# power.net
KiCad netlist of a schematic drawn in Altium Designer
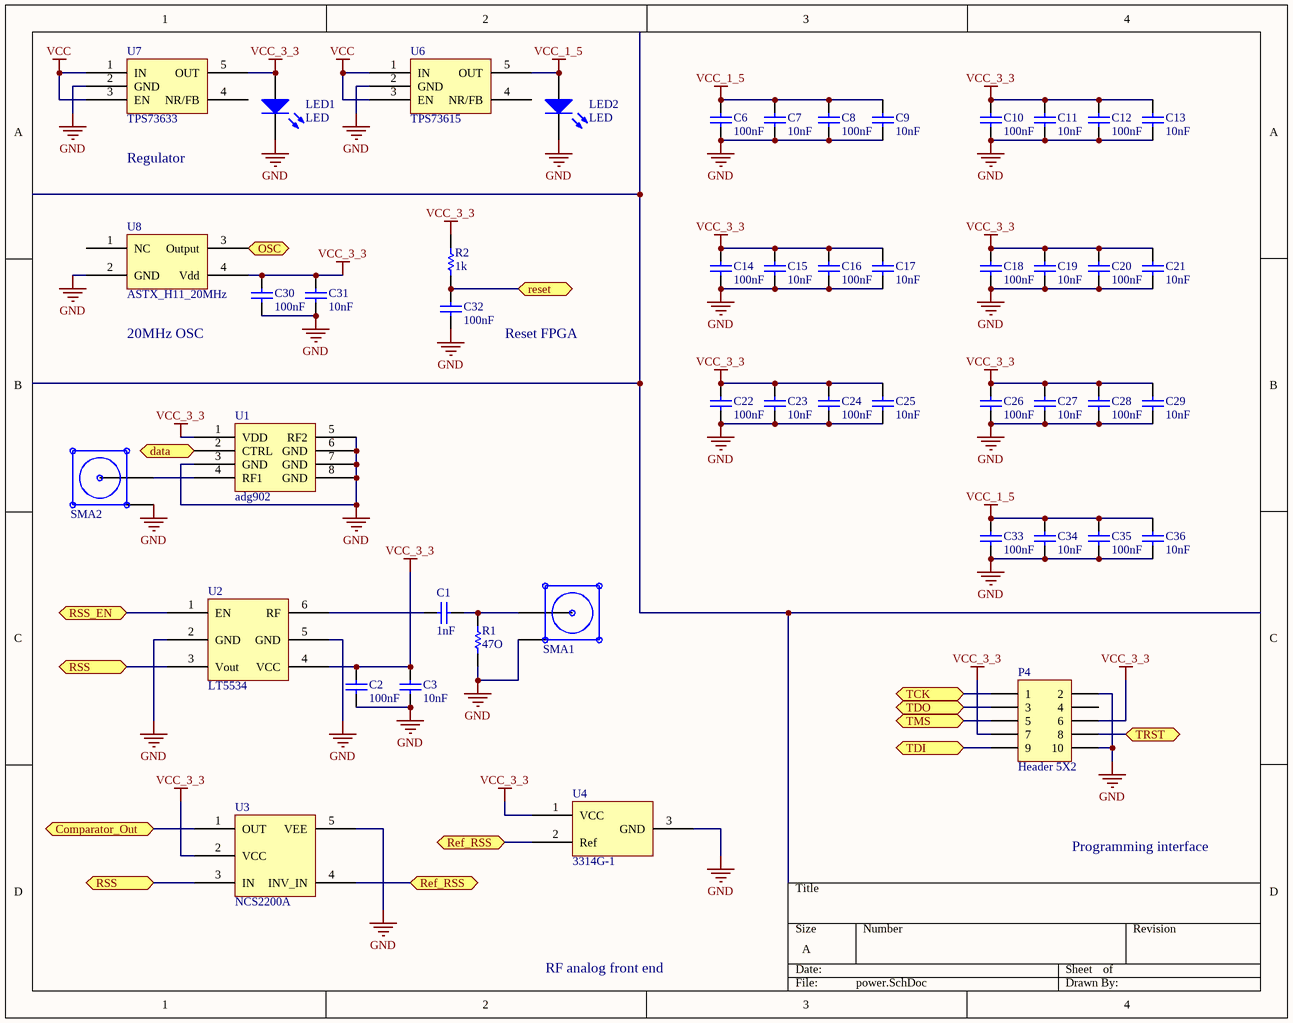
[diagram p0: power.SchDoc]

(export (version "E")
  (design (tool "Eeschema 10.0.6"))
  (components
    (comp (ref "C1")
      (value "1nF")
      (footprint "0603")
      (description "Ceramic Capacitor (Surface Mount)")
      (fields (field (name "MANUFACTURER") "Generic Ceramic Chip Cap (TBD)") (field (name "Comment") "Cap"))
      (libsource (lib "wisp") (part "Cap"))
    )
    (comp (ref "C2")
      (value "100nF")
      (footprint "0603")
      (description "Ceramic Capacitor (Surface Mount)")
      (fields (field (name "MANUFACTURER") "Generic Ceramic Chip Cap (TBD)") (field (name "Comment") "Cap"))
      (libsource (lib "wisp") (part "Cap"))
    )
    (comp (ref "C3")
      (value "10nF")
      (footprint "0603")
      (description "Ceramic Capacitor (Surface Mount)")
      (fields (field (name "MANUFACTURER") "Generic Ceramic Chip Cap (TBD)") (field (name "Comment") "Cap"))
      (libsource (lib "wisp") (part "Cap"))
    )
    (comp (ref "C6")
      (value "100nF")
      (footprint "0603")
      (description "Ceramic Capacitor (Surface Mount)")
      (fields (field (name "MANUFACTURER") "Generic Ceramic Chip Cap (TBD)") (field (name "Comment") "Cap"))
      (libsource (lib "wisp") (part "Cap"))
    )
    (comp (ref "C7")
      (value "10nF")
      (footprint "0603")
      (description "Ceramic Capacitor (Surface Mount)")
      (fields (field (name "MANUFACTURER") "Generic Ceramic Chip Cap (TBD)") (field (name "Comment") "Cap"))
      (libsource (lib "wisp") (part "Cap"))
    )
    (comp (ref "C8")
      (value "100nF")
      (footprint "0603")
      (description "Ceramic Capacitor (Surface Mount)")
      (fields (field (name "MANUFACTURER") "Generic Ceramic Chip Cap (TBD)") (field (name "Comment") "Cap"))
      (libsource (lib "wisp") (part "Cap"))
    )
    (comp (ref "C9")
      (value "10nF")
      (footprint "0603")
      (description "Ceramic Capacitor (Surface Mount)")
      (fields (field (name "MANUFACTURER") "Generic Ceramic Chip Cap (TBD)") (field (name "Comment") "Cap"))
      (libsource (lib "wisp") (part "Cap"))
    )
    (comp (ref "C10")
      (value "100nF")
      (footprint "0603")
      (description "Ceramic Capacitor (Surface Mount)")
      (fields (field (name "MANUFACTURER") "Generic Ceramic Chip Cap (TBD)") (field (name "Comment") "Cap"))
      (libsource (lib "wisp") (part "Cap"))
    )
    (comp (ref "C11")
      (value "10nF")
      (footprint "0603")
      (description "Ceramic Capacitor (Surface Mount)")
      (fields (field (name "MANUFACTURER") "Generic Ceramic Chip Cap (TBD)") (field (name "Comment") "Cap"))
      (libsource (lib "wisp") (part "Cap"))
    )
    (comp (ref "C12")
      (value "100nF")
      (footprint "0603")
      (description "Ceramic Capacitor (Surface Mount)")
      (fields (field (name "MANUFACTURER") "Generic Ceramic Chip Cap (TBD)") (field (name "Comment") "Cap"))
      (libsource (lib "wisp") (part "Cap"))
    )
    (comp (ref "C13")
      (value "10nF")
      (footprint "0603")
      (description "Ceramic Capacitor (Surface Mount)")
      (fields (field (name "MANUFACTURER") "Generic Ceramic Chip Cap (TBD)") (field (name "Comment") "Cap"))
      (libsource (lib "wisp") (part "Cap"))
    )
    (comp (ref "C14")
      (value "100nF")
      (footprint "0603")
      (description "Ceramic Capacitor (Surface Mount)")
      (fields (field (name "MANUFACTURER") "Generic Ceramic Chip Cap (TBD)") (field (name "Comment") "Cap"))
      (libsource (lib "wisp") (part "Cap"))
    )
    (comp (ref "C15")
      (value "10nF")
      (footprint "0603")
      (description "Ceramic Capacitor (Surface Mount)")
      (fields (field (name "MANUFACTURER") "Generic Ceramic Chip Cap (TBD)") (field (name "Comment") "Cap"))
      (libsource (lib "wisp") (part "Cap"))
    )
    (comp (ref "C16")
      (value "100nF")
      (footprint "0603")
      (description "Ceramic Capacitor (Surface Mount)")
      (fields (field (name "MANUFACTURER") "Generic Ceramic Chip Cap (TBD)") (field (name "Comment") "Cap"))
      (libsource (lib "wisp") (part "Cap"))
    )
    (comp (ref "C17")
      (value "10nF")
      (footprint "0603")
      (description "Ceramic Capacitor (Surface Mount)")
      (fields (field (name "MANUFACTURER") "Generic Ceramic Chip Cap (TBD)") (field (name "Comment") "Cap"))
      (libsource (lib "wisp") (part "Cap"))
    )
    (comp (ref "C18")
      (value "100nF")
      (footprint "0603")
      (description "Ceramic Capacitor (Surface Mount)")
      (fields (field (name "MANUFACTURER") "Generic Ceramic Chip Cap (TBD)") (field (name "Comment") "Cap"))
      (libsource (lib "wisp") (part "Cap"))
    )
    (comp (ref "C19")
      (value "10nF")
      (footprint "0603")
      (description "Ceramic Capacitor (Surface Mount)")
      (fields (field (name "MANUFACTURER") "Generic Ceramic Chip Cap (TBD)") (field (name "Comment") "Cap"))
      (libsource (lib "wisp") (part "Cap"))
    )
    (comp (ref "C20")
      (value "100nF")
      (footprint "0603")
      (description "Ceramic Capacitor (Surface Mount)")
      (fields (field (name "MANUFACTURER") "Generic Ceramic Chip Cap (TBD)") (field (name "Comment") "Cap"))
      (libsource (lib "wisp") (part "Cap"))
    )
    (comp (ref "C21")
      (value "10nF")
      (footprint "0603")
      (description "Ceramic Capacitor (Surface Mount)")
      (fields (field (name "MANUFACTURER") "Generic Ceramic Chip Cap (TBD)") (field (name "Comment") "Cap"))
      (libsource (lib "wisp") (part "Cap"))
    )
    (comp (ref "C22")
      (value "100nF")
      (footprint "0603")
      (description "Ceramic Capacitor (Surface Mount)")
      (fields (field (name "MANUFACTURER") "Generic Ceramic Chip Cap (TBD)") (field (name "Comment") "Cap"))
      (libsource (lib "wisp") (part "Cap"))
    )
    (comp (ref "C23")
      (value "10nF")
      (footprint "0603")
      (description "Ceramic Capacitor (Surface Mount)")
      (fields (field (name "MANUFACTURER") "Generic Ceramic Chip Cap (TBD)") (field (name "Comment") "Cap"))
      (libsource (lib "wisp") (part "Cap"))
    )
    (comp (ref "C24")
      (value "100nF")
      (footprint "0603")
      (description "Ceramic Capacitor (Surface Mount)")
      (fields (field (name "MANUFACTURER") "Generic Ceramic Chip Cap (TBD)") (field (name "Comment") "Cap"))
      (libsource (lib "wisp") (part "Cap"))
    )
    (comp (ref "C25")
      (value "10nF")
      (footprint "0603")
      (description "Ceramic Capacitor (Surface Mount)")
      (fields (field (name "MANUFACTURER") "Generic Ceramic Chip Cap (TBD)") (field (name "Comment") "Cap"))
      (libsource (lib "wisp") (part "Cap"))
    )
    (comp (ref "C26")
      (value "100nF")
      (footprint "0603")
      (description "Ceramic Capacitor (Surface Mount)")
      (fields (field (name "MANUFACTURER") "Generic Ceramic Chip Cap (TBD)") (field (name "Comment") "Cap"))
      (libsource (lib "wisp") (part "Cap"))
    )
    (comp (ref "C27")
      (value "10nF")
      (footprint "0603")
      (description "Ceramic Capacitor (Surface Mount)")
      (fields (field (name "MANUFACTURER") "Generic Ceramic Chip Cap (TBD)") (field (name "Comment") "Cap"))
      (libsource (lib "wisp") (part "Cap"))
    )
    (comp (ref "C28")
      (value "100nF")
      (footprint "0603")
      (description "Ceramic Capacitor (Surface Mount)")
      (fields (field (name "MANUFACTURER") "Generic Ceramic Chip Cap (TBD)") (field (name "Comment") "Cap"))
      (libsource (lib "wisp") (part "Cap"))
    )
    (comp (ref "C29")
      (value "10nF")
      (footprint "0603")
      (description "Ceramic Capacitor (Surface Mount)")
      (fields (field (name "MANUFACTURER") "Generic Ceramic Chip Cap (TBD)") (field (name "Comment") "Cap"))
      (libsource (lib "wisp") (part "Cap"))
    )
    (comp (ref "C30")
      (value "100nF")
      (footprint "0603")
      (description "Ceramic Capacitor (Surface Mount)")
      (fields (field (name "MANUFACTURER") "Generic Ceramic Chip Cap (TBD)") (field (name "Comment") "Cap"))
      (libsource (lib "wisp") (part "Cap"))
    )
    (comp (ref "C31")
      (value "10nF")
      (footprint "0603")
      (description "Ceramic Capacitor (Surface Mount)")
      (fields (field (name "MANUFACTURER") "Generic Ceramic Chip Cap (TBD)") (field (name "Comment") "Cap"))
      (libsource (lib "wisp") (part "Cap"))
    )
    (comp (ref "C32")
      (value "100nF")
      (footprint "0603")
      (description "Ceramic Capacitor (Surface Mount)")
      (fields (field (name "MANUFACTURER") "Generic Ceramic Chip Cap (TBD)") (field (name "Comment") "Cap"))
      (libsource (lib "wisp") (part "Cap"))
    )
    (comp (ref "C33")
      (value "100nF")
      (footprint "0603")
      (description "Ceramic Capacitor (Surface Mount)")
      (fields (field (name "MANUFACTURER") "Generic Ceramic Chip Cap (TBD)") (field (name "Comment") "Cap"))
      (libsource (lib "wisp") (part "Cap"))
    )
    (comp (ref "C34")
      (value "10nF")
      (footprint "0603")
      (description "Ceramic Capacitor (Surface Mount)")
      (fields (field (name "MANUFACTURER") "Generic Ceramic Chip Cap (TBD)") (field (name "Comment") "Cap"))
      (libsource (lib "wisp") (part "Cap"))
    )
    (comp (ref "C35")
      (value "100nF")
      (footprint "0603")
      (description "Ceramic Capacitor (Surface Mount)")
      (fields (field (name "MANUFACTURER") "Generic Ceramic Chip Cap (TBD)") (field (name "Comment") "Cap"))
      (libsource (lib "wisp") (part "Cap"))
    )
    (comp (ref "C36")
      (value "10nF")
      (footprint "0603")
      (description "Ceramic Capacitor (Surface Mount)")
      (fields (field (name "MANUFACTURER") "Generic Ceramic Chip Cap (TBD)") (field (name "Comment") "Cap"))
      (libsource (lib "wisp") (part "Cap"))
    )
    (comp (ref "LED1") (value "LED") (libsource (lib "pengyulib") (part "LED")))
    (comp (ref "LED2") (value "LED") (libsource (lib "pengyulib") (part "LED")))
    (comp (ref "P4")
      (value "Header 5X2")
      (footprint "HDR2X5")
      (description "Header, 5-Pin, Dual row")
      (fields (field (name "PUBLISHER") "Altium Limited"))
      (libsource (lib "Miscellaneous Connectors") (part "Header 5X2"))
    )
    (comp (ref "R1")
      (value "47O")
      (footprint "0603")
      (description "Chip Resistor (Surface Mount)")
      (fields (field (name "MANUFACTURER") "Generic Chip Res (TBD)") (field (name "Comment") "Res"))
      (libsource (lib "wisp") (part "Res"))
    )
    (comp (ref "R2")
      (value "1k")
      (footprint "0603")
      (description "Chip Resistor (Surface Mount)")
      (fields (field (name "MANUFACTURER") "Generic Chip Res (TBD)") (field (name "Comment") "Res"))
      (libsource (lib "wisp") (part "Res"))
    )
    (comp (ref "SMA1")
      (value "SMA - Hole - 5 Pin")
      (footprint "SMA - Hole - 5 Pin")
      (description "SMA - Through Hole Connector")
      (libsource (lib "wisp") (part "SMA - Hole - 5 Pin"))
    )
    (comp (ref "SMA2")
      (value "SMA - Hole - 5 Pin")
      (footprint "SMA - Hole - 5 Pin")
      (description "SMA - Through Hole Connector")
      (libsource (lib "wisp") (part "SMA - Hole - 5 Pin"))
    )
    (comp (ref "U1") (value "adg902") (footprint "ADG902") (libsource (lib "pengyulib") (part "adg902")))
    (comp (ref "U2") (value "LT5534") (footprint "LT5534") (libsource (lib "pengyulib") (part "LT55534")))
    (comp (ref "U3") (value "NCS2200A") (footprint "NCS2200") (libsource (lib "pengyulib") (part "NCS2200A")))
    (comp (ref "U4") (value "3314G-1") (footprint "3314G-1") (libsource (lib "pengyulib") (part "3314G-1")))
    (comp (ref "U6")
      (value "TPS73615")
      (footprint "TPS73633")
      (libsource (lib "pengyulib") (part "TPS73615"))
    )
    (comp (ref "U7")
      (value "TPS73633")
      (footprint "TPS73633")
      (libsource (lib "pengyulib") (part "TPS73633"))
    )
    (comp (ref "U8")
      (value "ASTX_H11_20MHz")
      (footprint "ASTX_H11")
      (libsource (lib "pengyulib") (part "ASTX_H11_20MHz"))
    )
  )
  (nets
    (net (code "1") (name "/Comparator_Out") (class "Default")
      (node (ref "U3") (pin "1") (pinfunction "OUT_1") (pintype "passive"))
    )
    (net (code "2") (name "/OSC") (class "Default")
      (node (ref "U8") (pin "3") (pinfunction "Output_3") (pintype "passive"))
    )
    (net (code "3") (name "/RSS") (class "Default")
      (node (ref "U2") (pin "3") (pinfunction "Vout_3") (pintype "passive"))
      (node (ref "U3") (pin "3") (pinfunction "IN_3") (pintype "passive"))
    )
    (net (code "4") (name "/RSS_EN") (class "Default")
      (node (ref "U2") (pin "1") (pinfunction "EN_1") (pintype "passive"))
    )
    (net (code "5") (name "/Ref_RSS") (class "Default")
      (node (ref "U3") (pin "4") (pinfunction "INV_IN_4") (pintype "passive"))
      (node (ref "U4") (pin "2") (pinfunction "Ref_2") (pintype "passive"))
    )
    (net (code "6") (name "/TCK") (class "Default")
      (node (ref "P4") (pin "1") (pinfunction "1_1") (pintype "passive"))
    )
    (net (code "7") (name "/TDI") (class "Default")
      (node (ref "P4") (pin "9") (pinfunction "9_9") (pintype "passive"))
    )
    (net (code "8") (name "/TDO") (class "Default")
      (node (ref "P4") (pin "3") (pinfunction "3_3") (pintype "passive"))
    )
    (net (code "9") (name "/TMS") (class "Default")
      (node (ref "P4") (pin "5") (pinfunction "5_5") (pintype "passive"))
    )
    (net (code "10") (name "/TRST") (class "Default")
      (node (ref "P4") (pin "8") (pinfunction "8_8") (pintype "passive"))
    )
    (net (code "11") (name "/data") (class "Default")
      (node (ref "U1") (pin "2") (pinfunction "CTRL_2") (pintype "passive"))
    )
    (net (code "12") (name "/reset") (class "Default")
      (node (ref "C32") (pin "2") (pinfunction "2_2") (pintype "passive"))
      (node (ref "R2") (pin "1") (pinfunction "1_1") (pintype "passive"))
    )
    (net (code "13") (name "GND") (class "Default")
      (node (ref "C10") (pin "1") (pinfunction "1_1") (pintype "passive"))
      (node (ref "C11") (pin "1") (pinfunction "1_1") (pintype "passive"))
      (node (ref "C12") (pin "1") (pinfunction "1_1") (pintype "passive"))
      (node (ref "C13") (pin "1") (pinfunction "1_1") (pintype "passive"))
      (node (ref "C14") (pin "1") (pinfunction "1_1") (pintype "passive"))
      (node (ref "C15") (pin "1") (pinfunction "1_1") (pintype "passive"))
      (node (ref "C16") (pin "1") (pinfunction "1_1") (pintype "passive"))
      (node (ref "C17") (pin "1") (pinfunction "1_1") (pintype "passive"))
      (node (ref "C18") (pin "1") (pinfunction "1_1") (pintype "passive"))
      (node (ref "C19") (pin "1") (pinfunction "1_1") (pintype "passive"))
      (node (ref "C2") (pin "1") (pinfunction "1_1") (pintype "passive"))
      (node (ref "C20") (pin "1") (pinfunction "1_1") (pintype "passive"))
      (node (ref "C21") (pin "1") (pinfunction "1_1") (pintype "passive"))
      (node (ref "C22") (pin "1") (pinfunction "1_1") (pintype "passive"))
      (node (ref "C23") (pin "1") (pinfunction "1_1") (pintype "passive"))
      (node (ref "C24") (pin "1") (pinfunction "1_1") (pintype "passive"))
      (node (ref "C25") (pin "1") (pinfunction "1_1") (pintype "passive"))
      (node (ref "C26") (pin "1") (pinfunction "1_1") (pintype "passive"))
      (node (ref "C27") (pin "1") (pinfunction "1_1") (pintype "passive"))
      (node (ref "C28") (pin "1") (pinfunction "1_1") (pintype "passive"))
      (node (ref "C29") (pin "1") (pinfunction "1_1") (pintype "passive"))
      (node (ref "C3") (pin "1") (pinfunction "1_1") (pintype "passive"))
      (node (ref "C30") (pin "1") (pinfunction "1_1") (pintype "passive"))
      (node (ref "C31") (pin "1") (pinfunction "1_1") (pintype "passive"))
      (node (ref "C32") (pin "1") (pinfunction "1_1") (pintype "passive"))
      (node (ref "C33") (pin "1") (pinfunction "1_1") (pintype "passive"))
      (node (ref "C34") (pin "1") (pinfunction "1_1") (pintype "passive"))
      (node (ref "C35") (pin "1") (pinfunction "1_1") (pintype "passive"))
      (node (ref "C36") (pin "1") (pinfunction "1_1") (pintype "passive"))
      (node (ref "C6") (pin "1") (pinfunction "1_1") (pintype "passive"))
      (node (ref "C7") (pin "1") (pinfunction "1_1") (pintype "passive"))
      (node (ref "C8") (pin "1") (pinfunction "1_1") (pintype "passive"))
      (node (ref "C9") (pin "1") (pinfunction "1_1") (pintype "passive"))
      (node (ref "LED1") (pin "2") (pinfunction "K_2") (pintype "passive"))
      (node (ref "LED2") (pin "2") (pinfunction "K_2") (pintype "passive"))
      (node (ref "P4") (pin "10") (pinfunction "10_10") (pintype "passive"))
      (node (ref "P4") (pin "2") (pinfunction "2_2") (pintype "passive"))
      (node (ref "R1") (pin "1") (pinfunction "1_1") (pintype "passive"))
      (node (ref "SMA1") (pin "1") (pinfunction "1_1") (pintype "passive"))
      (node (ref "SMA2") (pin "1") (pinfunction "1_1") (pintype "passive"))
      (node (ref "U1") (pin "3") (pinfunction "GND_3") (pintype "passive"))
      (node (ref "U1") (pin "5") (pinfunction "RF2_5") (pintype "passive"))
      (node (ref "U1") (pin "6") (pinfunction "GND_6") (pintype "passive"))
      (node (ref "U1") (pin "7") (pinfunction "GND_7") (pintype "passive"))
      (node (ref "U1") (pin "8") (pinfunction "GND_8") (pintype "passive"))
      (node (ref "U2") (pin "2") (pinfunction "GND_2") (pintype "passive"))
      (node (ref "U2") (pin "5") (pinfunction "GND_5") (pintype "passive"))
      (node (ref "U3") (pin "5") (pinfunction "VEE_5") (pintype "passive"))
      (node (ref "U4") (pin "3") (pinfunction "GND_3") (pintype "passive"))
      (node (ref "U6") (pin "2") (pinfunction "GND_2") (pintype "passive"))
      (node (ref "U7") (pin "2") (pinfunction "GND_2") (pintype "passive"))
      (node (ref "U8") (pin "2") (pinfunction "GND_2") (pintype "passive"))
    )
    (net (code "14") (name "Net-(C1-Pad2)") (class "Default")
      (node (ref "C1") (pin "2") (pinfunction "2_2") (pintype "passive"))
      (node (ref "R1") (pin "2") (pinfunction "2_2") (pintype "passive"))
      (node (ref "SMA1") (pin "2") (pinfunction "2_2") (pintype "passive"))
    )
    (net (code "15") (name "Net-(U1-RF1)") (class "Default")
      (node (ref "SMA2") (pin "2") (pinfunction "2_2") (pintype "passive"))
      (node (ref "U1") (pin "4") (pinfunction "RF1_4") (pintype "passive"))
    )
    (net (code "16") (name "Net-(U2-RF)") (class "Default")
      (node (ref "C1") (pin "1") (pinfunction "1_1") (pintype "passive"))
      (node (ref "U2") (pin "6") (pinfunction "RF_6") (pintype "passive"))
    )
    (net (code "17") (name "VCC") (class "Default")
      (node (ref "U6") (pin "1") (pinfunction "IN_1") (pintype "passive"))
      (node (ref "U6") (pin "3") (pinfunction "EN_3") (pintype "passive"))
      (node (ref "U7") (pin "1") (pinfunction "IN_1") (pintype "passive"))
      (node (ref "U7") (pin "3") (pinfunction "EN_3") (pintype "passive"))
    )
    (net (code "18") (name "VCC_1_5") (class "Default")
      (node (ref "C33") (pin "2") (pinfunction "2_2") (pintype "passive"))
      (node (ref "C34") (pin "2") (pinfunction "2_2") (pintype "passive"))
      (node (ref "C35") (pin "2") (pinfunction "2_2") (pintype "passive"))
      (node (ref "C36") (pin "2") (pinfunction "2_2") (pintype "passive"))
      (node (ref "C6") (pin "2") (pinfunction "2_2") (pintype "passive"))
      (node (ref "C7") (pin "2") (pinfunction "2_2") (pintype "passive"))
      (node (ref "C8") (pin "2") (pinfunction "2_2") (pintype "passive"))
      (node (ref "C9") (pin "2") (pinfunction "2_2") (pintype "passive"))
      (node (ref "LED2") (pin "1") (pinfunction "A_1") (pintype "passive"))
      (node (ref "U6") (pin "5") (pinfunction "OUT_5") (pintype "passive"))
    )
    (net (code "19") (name "VCC_3_3") (class "Default")
      (node (ref "C10") (pin "2") (pinfunction "2_2") (pintype "passive"))
      (node (ref "C11") (pin "2") (pinfunction "2_2") (pintype "passive"))
      (node (ref "C12") (pin "2") (pinfunction "2_2") (pintype "passive"))
      (node (ref "C13") (pin "2") (pinfunction "2_2") (pintype "passive"))
      (node (ref "C14") (pin "2") (pinfunction "2_2") (pintype "passive"))
      (node (ref "C15") (pin "2") (pinfunction "2_2") (pintype "passive"))
      (node (ref "C16") (pin "2") (pinfunction "2_2") (pintype "passive"))
      (node (ref "C17") (pin "2") (pinfunction "2_2") (pintype "passive"))
      (node (ref "C18") (pin "2") (pinfunction "2_2") (pintype "passive"))
      (node (ref "C19") (pin "2") (pinfunction "2_2") (pintype "passive"))
      (node (ref "C2") (pin "2") (pinfunction "2_2") (pintype "passive"))
      (node (ref "C20") (pin "2") (pinfunction "2_2") (pintype "passive"))
      (node (ref "C21") (pin "2") (pinfunction "2_2") (pintype "passive"))
      (node (ref "C22") (pin "2") (pinfunction "2_2") (pintype "passive"))
      (node (ref "C23") (pin "2") (pinfunction "2_2") (pintype "passive"))
      (node (ref "C24") (pin "2") (pinfunction "2_2") (pintype "passive"))
      (node (ref "C25") (pin "2") (pinfunction "2_2") (pintype "passive"))
      (node (ref "C26") (pin "2") (pinfunction "2_2") (pintype "passive"))
      (node (ref "C27") (pin "2") (pinfunction "2_2") (pintype "passive"))
      (node (ref "C28") (pin "2") (pinfunction "2_2") (pintype "passive"))
      (node (ref "C29") (pin "2") (pinfunction "2_2") (pintype "passive"))
      (node (ref "C3") (pin "2") (pinfunction "2_2") (pintype "passive"))
      (node (ref "C30") (pin "2") (pinfunction "2_2") (pintype "passive"))
      (node (ref "C31") (pin "2") (pinfunction "2_2") (pintype "passive"))
      (node (ref "LED1") (pin "1") (pinfunction "A_1") (pintype "passive"))
      (node (ref "P4") (pin "6") (pinfunction "6_6") (pintype "passive"))
      (node (ref "P4") (pin "7") (pinfunction "7_7") (pintype "passive"))
      (node (ref "R2") (pin "2") (pinfunction "2_2") (pintype "passive"))
      (node (ref "U1") (pin "1") (pinfunction "VDD_1") (pintype "passive"))
      (node (ref "U2") (pin "4") (pinfunction "VCC_4") (pintype "passive"))
      (node (ref "U3") (pin "2") (pinfunction "VCC_2") (pintype "passive"))
      (node (ref "U4") (pin "1") (pinfunction "VCC_1") (pintype "passive"))
      (node (ref "U7") (pin "5") (pinfunction "OUT_5") (pintype "passive"))
      (node (ref "U8") (pin "4") (pinfunction "Vdd_4") (pintype "passive"))
    )
    (net (code "20") (name "unconnected-(P4-Pad4)") (class "Default")
      (node (ref "P4") (pin "4") (pinfunction "4_4") (pintype "passive"))
    )
    (net (code "21") (name "unconnected-(U6-NR{slash}FB-Pad4)") (class "Default")
      (node (ref "U6") (pin "4") (pinfunction "NR/FB_4") (pintype "passive"))
    )
    (net (code "22") (name "unconnected-(U7-NR{slash}FB-Pad4)") (class "Default")
      (node (ref "U7") (pin "4") (pinfunction "NR/FB_4") (pintype "passive"))
    )
    (net (code "23") (name "unconnected-(U8-NC-Pad1)") (class "Default")
      (node (ref "U8") (pin "1") (pinfunction "NC_1") (pintype "passive"))
    )
  )
)
